# interface.net
KiCad netlist of a schematic drawn in Altium Designer
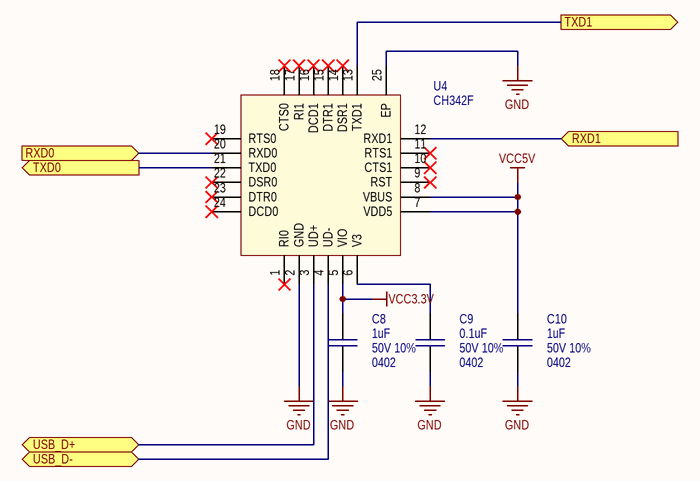
[diagram p0: interface.SchDoc]

(export (version "E")
  (design (tool "Eeschema 10.0.6"))
  (components
    (comp (ref "C8")
      (value "1uF")
      (footprint "C_0402")
      (description "Capacitor")
      (fields
        (field (name "PART") "CC0402KRX5R9BB105")
        (field (name "CASE/PACKAGE") "0402")
        (field (name "TOLERANCE") "50V 10%")
        (field (name "Comment") "C0402")
      )
      (libsource (lib "capacitors") (part "C0402"))
    )
    (comp (ref "C9")
      (value "0.1uF")
      (footprint "C_0402")
      (description "Capacitor")
      (fields
        (field (name "PART") "CC0402KRX5R9BB104")
        (field (name "CASE/PACKAGE") "0402")
        (field (name "TOLERANCE") "50V 10%")
        (field (name "Comment") "C0402")
      )
      (libsource (lib "capacitors") (part "C0402"))
    )
    (comp (ref "C10")
      (value "1uF")
      (footprint "C_0402")
      (description "Capacitor")
      (fields
        (field (name "PART") "CC0402KRX5R9BB105")
        (field (name "CASE/PACKAGE") "0402")
        (field (name "TOLERANCE") "50V 10%")
        (field (name "Comment") "C0402")
      )
      (libsource (lib "capacitors") (part "C0402"))
    )
    (comp (ref "U4")
      (value "CH342F")
      (footprint "QFN50P400X400X80-25N-D")
      (libsource (lib "discret_ic") (part "CH342F"))
    )
  )
  (nets
    (net (code "1") (name "/RXD0") (class "Default")
      (node (ref "U4") (pin "20") (pinfunction "RXD0_20") (pintype "passive"))
    )
    (net (code "2") (name "/RXD1") (class "Default")
      (node (ref "U4") (pin "12") (pinfunction "RXD1_12") (pintype "passive"))
    )
    (net (code "3") (name "/TXD0") (class "Default")
      (node (ref "U4") (pin "21") (pinfunction "TXD0_21") (pintype "passive"))
    )
    (net (code "4") (name "/TXD1") (class "Default")
      (node (ref "U4") (pin "13") (pinfunction "TXD1_13") (pintype "passive"))
    )
    (net (code "5") (name "/USB_D+") (class "Default")
      (node (ref "U4") (pin "3") (pinfunction "UD+_3") (pintype "passive"))
    )
    (net (code "6") (name "/USB_D-") (class "Default")
      (node (ref "U4") (pin "4") (pinfunction "UD-_4") (pintype "passive"))
    )
    (net (code "7") (name "GND") (class "Default")
      (node (ref "C10") (pin "1") (pinfunction "1_1") (pintype "passive"))
      (node (ref "C8") (pin "1") (pinfunction "1_1") (pintype "passive"))
      (node (ref "C9") (pin "1") (pinfunction "1_1") (pintype "passive"))
      (node (ref "U4") (pin "2") (pinfunction "GND_2") (pintype "passive"))
      (node (ref "U4") (pin "25") (pinfunction "EP_25") (pintype "passive"))
    )
    (net (code "8") (name "Net-(U4-V3)") (class "Default")
      (node (ref "C9") (pin "2") (pinfunction "2_2") (pintype "passive"))
      (node (ref "U4") (pin "6") (pinfunction "V3_6") (pintype "passive"))
    )
    (net (code "9") (name "VCC3.3V") (class "Default")
      (node (ref "C8") (pin "2") (pinfunction "2_2") (pintype "passive"))
      (node (ref "U4") (pin "5") (pinfunction "VIO_5") (pintype "passive"))
    )
    (net (code "10") (name "VCC5V") (class "Default")
      (node (ref "C10") (pin "2") (pinfunction "2_2") (pintype "passive"))
      (node (ref "U4") (pin "7") (pinfunction "VDD5_7") (pintype "passive"))
      (node (ref "U4") (pin "8") (pinfunction "VBUS_8") (pintype "passive"))
    )
    (net (code "11") (name "unconnected-(U4-CTS0-Pad18)") (class "Default")
      (node (ref "U4") (pin "18") (pinfunction "CTS0_18") (pintype "passive+no_connect"))
    )
    (net (code "12") (name "unconnected-(U4-CTS1-Pad10)") (class "Default")
      (node (ref "U4") (pin "10") (pinfunction "CTS1_10") (pintype "passive+no_connect"))
    )
    (net (code "13") (name "unconnected-(U4-DCD0-Pad24)") (class "Default")
      (node (ref "U4") (pin "24") (pinfunction "DCD0_24") (pintype "passive+no_connect"))
    )
    (net (code "14") (name "unconnected-(U4-DCD1-Pad16)") (class "Default")
      (node (ref "U4") (pin "16") (pinfunction "DCD1_16") (pintype "passive+no_connect"))
    )
    (net (code "15") (name "unconnected-(U4-DSR0-Pad22)") (class "Default")
      (node (ref "U4") (pin "22") (pinfunction "DSR0_22") (pintype "passive+no_connect"))
    )
    (net (code "16") (name "unconnected-(U4-DSR1-Pad14)") (class "Default")
      (node (ref "U4") (pin "14") (pinfunction "DSR1_14") (pintype "passive+no_connect"))
    )
    (net (code "17") (name "unconnected-(U4-DTR0-Pad23)") (class "Default")
      (node (ref "U4") (pin "23") (pinfunction "DTR0_23") (pintype "passive+no_connect"))
    )
    (net (code "18") (name "unconnected-(U4-DTR1-Pad15)") (class "Default")
      (node (ref "U4") (pin "15") (pinfunction "DTR1_15") (pintype "passive+no_connect"))
    )
    (net (code "19") (name "unconnected-(U4-RI0-Pad1)") (class "Default")
      (node (ref "U4") (pin "1") (pinfunction "RI0_1") (pintype "passive+no_connect"))
    )
    (net (code "20") (name "unconnected-(U4-RI1-Pad17)") (class "Default")
      (node (ref "U4") (pin "17") (pinfunction "RI1_17") (pintype "passive+no_connect"))
    )
    (net (code "21") (name "unconnected-(U4-RST-Pad9)") (class "Default")
      (node (ref "U4") (pin "9") (pinfunction "RST_9") (pintype "passive+no_connect"))
    )
    (net (code "22") (name "unconnected-(U4-RTS0-Pad19)") (class "Default")
      (node (ref "U4") (pin "19") (pinfunction "RTS0_19") (pintype "passive+no_connect"))
    )
    (net (code "23") (name "unconnected-(U4-RTS1-Pad11)") (class "Default")
      (node (ref "U4") (pin "11") (pinfunction "RTS1_11") (pintype "passive+no_connect"))
    )
  )
)
